# 10-Power_5v0.net
KiCad netlist of a schematic drawn in Altium Designer
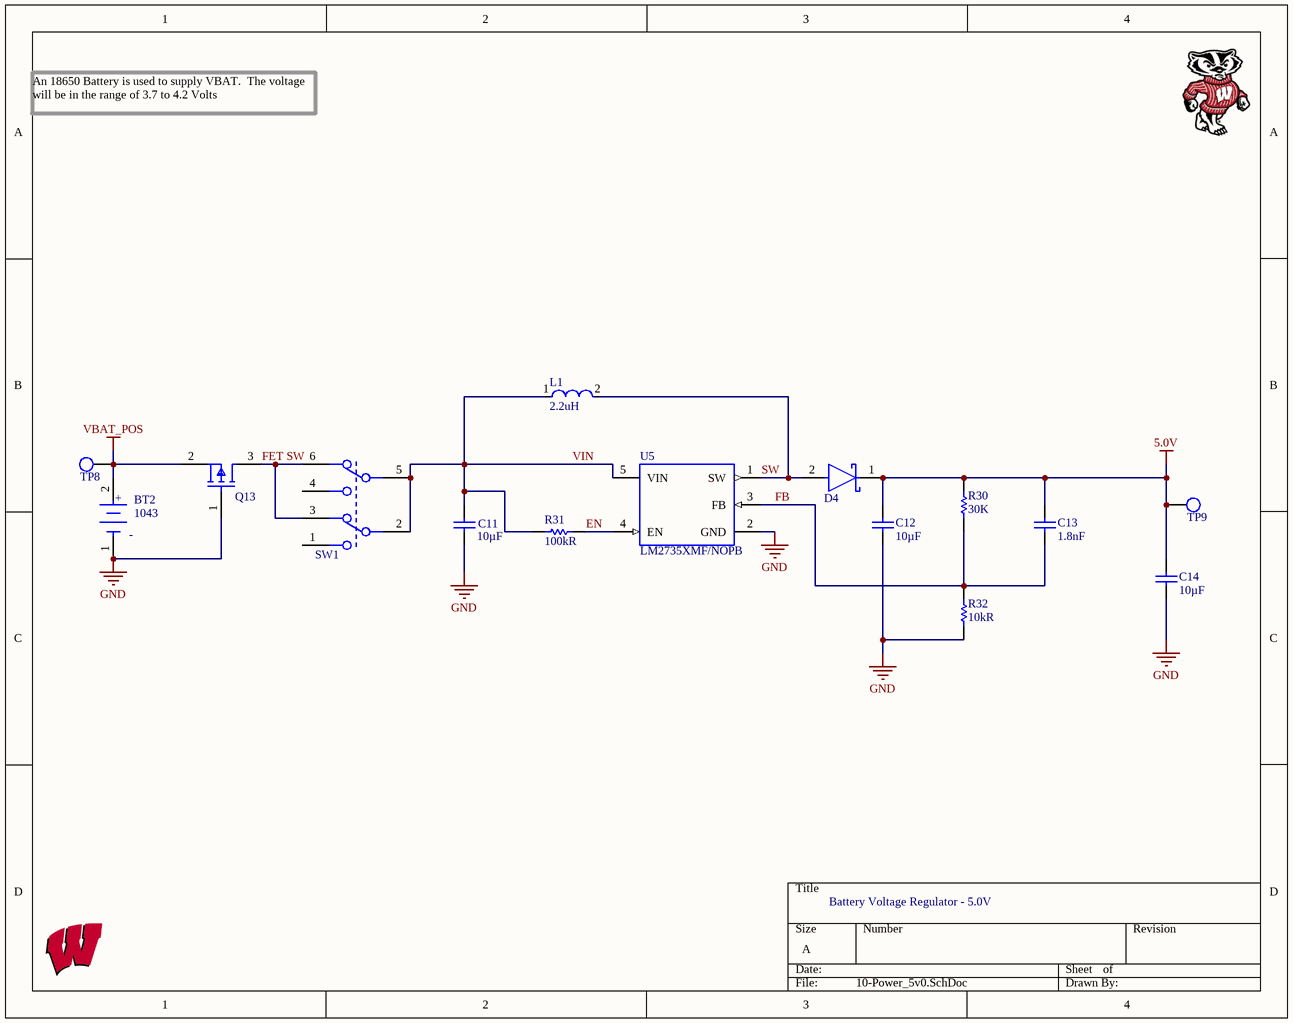
[diagram p0: 10-Power_5v0.SchDoc]

(export (version "E")
  (design (tool "Eeschema 10.0.6"))
  (components
    (comp (ref "BT2")
      (value "1043")
      (footprint "Keystone_1043_0")
      (description "Cylindrical Battery Contacts, Clips, Holders & Springs 18650 PCB PLASTIC BATT HLDR THM 1 CELL")
      (fields (field (name "MANUFACTURER PART NUMBER 1") "1043"))
      (libsource (lib "Battery") (part "1043"))
    )
    (comp (ref "C11")
      (value "10µF")
      (footprint "CAP_0805")
      (description "CAP CER 10UF 10V X5R 0805")
      (fields
        (field (name "MANUFACTURER") "Samsung Electro-Mechanics America, Inc.")
        (field (name "MANUFACTURER PART NUMBER") "CL21A106KPCLQNC")
      )
      (libsource (lib "Cap_Ceramic") (part "CAP_0805_U_010_00"))
    )
    (comp (ref "C12")
      (value "10µF")
      (footprint "CAP_0805")
      (description "CAP CER 10UF 10V X5R 0805")
      (fields
        (field (name "MANUFACTURER") "Samsung Electro-Mechanics America, Inc.")
        (field (name "MANUFACTURER PART NUMBER") "CL21A106KPCLQNC")
      )
      (libsource (lib "Cap_Ceramic") (part "CAP_0805_U_010_00"))
    )
    (comp (ref "C13")
      (value "CAP_0805_N_001_80")
      (footprint "CAP_0805")
      (fields
        (field (name "TOLERANCE") "5%")
        (field (name "VOLTAGE") "50V")
        (field (name "CAPACITANCE") "1.8nF")
      )
      (libsource (lib "Cap_Ceramic") (part "CAP_0805_N_001_80"))
    )
    (comp (ref "C14")
      (value "10µF")
      (footprint "CAP_0805")
      (description "CAP CER 10UF 10V X5R 0805")
      (fields
        (field (name "MANUFACTURER") "Samsung Electro-Mechanics America, Inc.")
        (field (name "MANUFACTURER PART NUMBER") "CL21A106KPCLQNC")
      )
      (libsource (lib "Cap_Ceramic") (part "CAP_0805_U_010_00"))
    )
    (comp (ref "D4")
      (value "SM5817PL-TP")
      (footprint "On_Semiconductor_425-04_IPC_A")
      (description "DIODE SCHOTTKY 20V 1A SOD123FL")
      (libsource (lib "Diodes") (part "SM5817PL-TP"))
    )
    (comp (ref "L1")
      (value "NRS4018T2R2MDGJ")
      (footprint "IND_TAIYO_NRS4018_TAY")
      (description "Inductor Power Shielded Wirewound 2.2uH 20% 100KHz Ferrite 2.2A 0.0504Ohm DCR 1515 T/R")
      (fields (field (name "TOLERANCE") "20%") (field (name "INDUCTANCE") "2.2uH"))
      (libsource (lib "Inductors") (part "NRS4018T2R2MDGJ"))
    )
    (comp (ref "Q13")
      (value "SSM3J328R,LF")
      (footprint "SOT-23_M")
      (description "MOSFET P-CH 20V 6A SOT23F")
      (libsource (lib "Transistors") (part "SSM3J328R,LF"))
    )
    (comp (ref "R30")
      (value "30K")
      (footprint "RES_0805")
      (description "Res Thick Film 0805 30K Ohm 1% 0.125W(1/8W) ±100ppm/°C Pad SMD Automotive T/R")
      (fields (field (name "TOLERANCE") "1%") (field (name "RESISTANCE") "30K"))
      (libsource (lib "Resistors") (part "RES_0805_K_030.00"))
    )
    (comp (ref "R31")
      (value "RES_0805_K_010.00")
      (footprint "RES_0805")
      (description "RES SMD 10K OHM 1% 1/8W 0805")
      (fields (field (name "TOLERANCE") "1%") (field (name "RESISTANCE") "100kR"))
      (libsource (lib "Resistors") (part "RES_0805_K_010.00"))
    )
    (comp (ref "R32")
      (value "RES_0805_K_010.00")
      (footprint "RES_0805")
      (description "RES SMD 10K OHM 1% 1/8W 0805")
      (fields (field (name "TOLERANCE") "1%") (field (name "RESISTANCE") "10kR"))
      (libsource (lib "Resistors") (part "RES_0805_K_010.00"))
    )
    (comp (ref "SW1")
      (value "JS202011SCQN")
      (footprint "C&K_Components_0_MFG")
      (description "C & K COMPONENTS - JS202011SCQN - SWITCH, DPDT, 0.6A, 6VDC, SMD")
      (libsource (lib "Switches") (part "JS202011SCQN"))
    )
    (comp (ref "TP8")
      (value "TP_1206")
      (footprint "TP-SMC-1206")
      (description "Test Point SMD 1206")
      (fields
        (field (name "MANUFACTURER") "TE Connectivity (Tyco Electronics)")
        (field (name "MANUFACTURER PART NUMBER") "1625854-1")
      )
      (libsource (lib "Mechanical") (part "TP_1206"))
    )
    (comp (ref "TP9")
      (value "TP_1206")
      (footprint "TP-SMC-1206")
      (description "Test Point SMD 1206")
      (fields
        (field (name "MANUFACTURER") "TE Connectivity (Tyco Electronics)")
        (field (name "MANUFACTURER PART NUMBER") "1625854-1")
      )
      (libsource (lib "Mechanical") (part "TP_1206"))
    )
    (comp (ref "U5")
      (value "LM2735XMF-NOPB")
      (footprint "Texas_Instruments_DBV0005A_0")
      (description "IC REG MULT CONFG ADJ 2.1A SOT23")
      (fields (field (name "MANUFACTURER PART NUMBER 1") "LM2735XMF/NOPB"))
      (libsource (lib "Regulators") (part "LM2735XMF-NOPB"))
    )
  )
  (nets
    (net (code "1") (name "/EN") (class "Default")
      (node (ref "R31") (pin "1") (pinfunction "1_1") (pintype "passive"))
      (node (ref "U5") (pin "4") (pinfunction "EN_4") (pintype "input"))
    )
    (net (code "2") (name "/FB") (class "Default")
      (node (ref "C13") (pin "1") (pinfunction "1_1") (pintype "passive"))
      (node (ref "R30") (pin "2") (pinfunction "2_2") (pintype "passive"))
      (node (ref "R32") (pin "2") (pinfunction "2_2") (pintype "passive"))
      (node (ref "U5") (pin "3") (pinfunction "FB_3") (pintype "input"))
    )
    (net (code "3") (name "/FET SW") (class "Default")
      (node (ref "Q13") (pin "3") (pinfunction "Drain_3") (pintype "passive"))
      (node (ref "SW1") (pin "3") (pinfunction "3_3") (pintype "passive"))
      (node (ref "SW1") (pin "6") (pinfunction "6_6") (pintype "passive"))
    )
    (net (code "4") (name "/SW") (class "Default")
      (node (ref "D4") (pin "2") (pinfunction "A_2") (pintype "passive"))
      (node (ref "L1") (pin "2") (pinfunction "2_2") (pintype "passive"))
      (node (ref "U5") (pin "1") (pinfunction "SW_1") (pintype "output"))
    )
    (net (code "5") (name "/VIN") (class "Default")
      (node (ref "C11") (pin "2") (pinfunction "2_2") (pintype "passive"))
      (node (ref "L1") (pin "1") (pinfunction "1_1") (pintype "passive"))
      (node (ref "R31") (pin "2") (pinfunction "2_2") (pintype "passive"))
      (node (ref "SW1") (pin "2") (pinfunction "2_2") (pintype "passive"))
      (node (ref "SW1") (pin "5") (pinfunction "5_5") (pintype "passive"))
      (node (ref "U5") (pin "5") (pinfunction "VIN_5") (pintype "power_in"))
    )
    (net (code "6") (name "5.0V") (class "Default")
      (node (ref "C12") (pin "2") (pinfunction "2_2") (pintype "passive"))
      (node (ref "C13") (pin "2") (pinfunction "2_2") (pintype "passive"))
      (node (ref "C14") (pin "2") (pinfunction "2_2") (pintype "passive"))
      (node (ref "D4") (pin "1") (pinfunction "C_1") (pintype "passive"))
      (node (ref "R30") (pin "1") (pinfunction "1_1") (pintype "passive"))
      (node (ref "TP9") (pin "1") (pintype "passive"))
    )
    (net (code "7") (name "GND") (class "Default")
      (node (ref "BT2") (pin "1") (pinfunction "C_1") (pintype "passive"))
      (node (ref "C11") (pin "1") (pinfunction "1_1") (pintype "passive"))
      (node (ref "C12") (pin "1") (pinfunction "1_1") (pintype "passive"))
      (node (ref "C14") (pin "1") (pinfunction "1_1") (pintype "passive"))
      (node (ref "Q13") (pin "1") (pinfunction "Gate_1") (pintype "passive"))
      (node (ref "R32") (pin "1") (pinfunction "1_1") (pintype "passive"))
      (node (ref "U5") (pin "2") (pinfunction "GND_2") (pintype "power_in"))
    )
    (net (code "8") (name "VBAT_POS") (class "Default")
      (node (ref "BT2") (pin "2") (pinfunction "A_2") (pintype "passive"))
      (node (ref "Q13") (pin "2") (pinfunction "Source_2") (pintype "passive"))
      (node (ref "TP8") (pin "1") (pintype "passive"))
    )
    (net (code "9") (name "unconnected-(SW1-Pad1)") (class "Default")
      (node (ref "SW1") (pin "1") (pinfunction "1_1") (pintype "passive"))
    )
    (net (code "10") (name "unconnected-(SW1-Pad4)") (class "Default")
      (node (ref "SW1") (pin "4") (pinfunction "4_4") (pintype "passive"))
    )
  )
)
